# Prototype.net
KiCad netlist of a schematic drawn in EAGLE
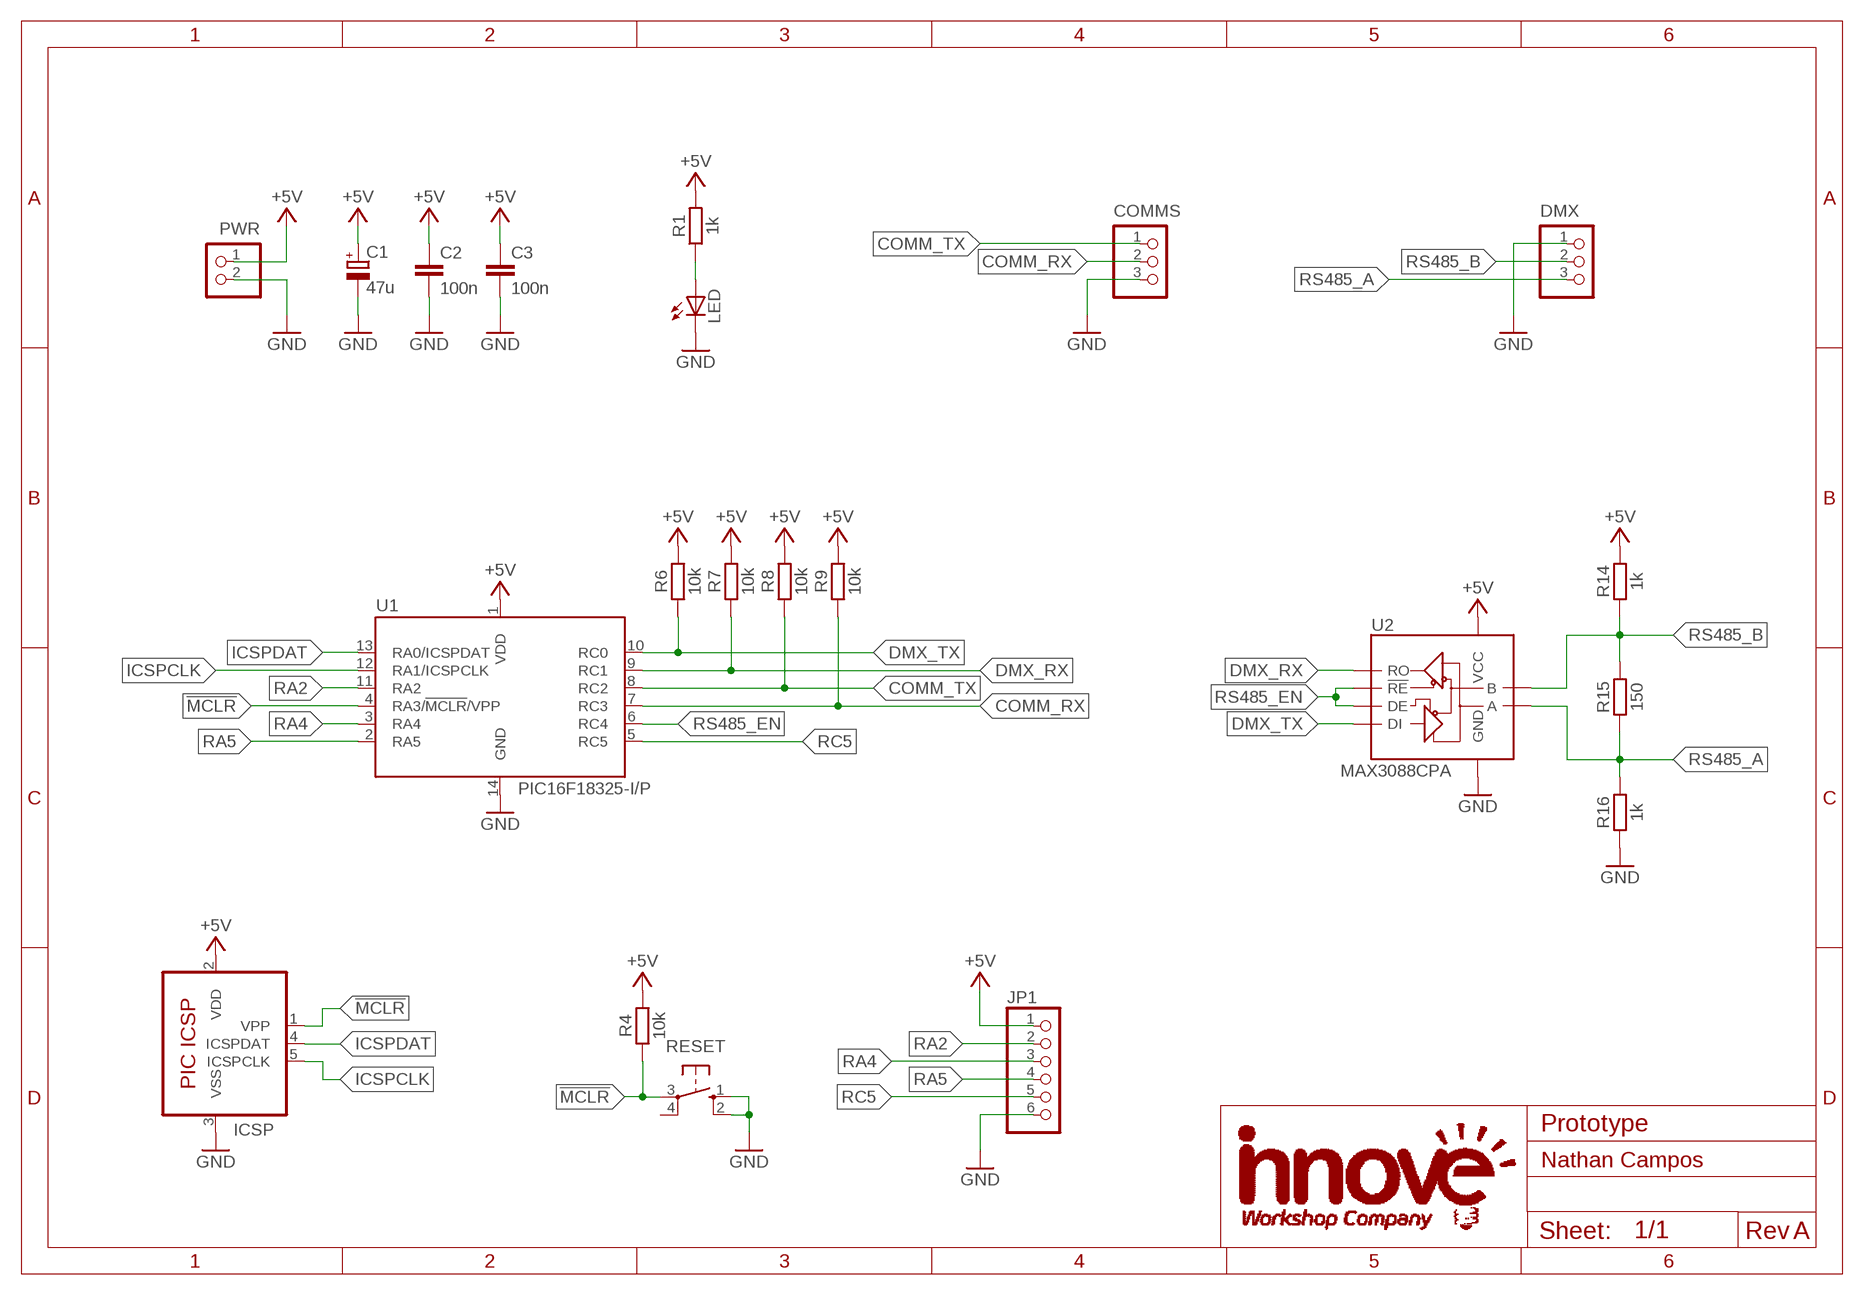
[diagram p0: schematic, sheet 1]

(export (version "E")
  (design (tool "Eeschema 10.0.6"))
  (components
    (comp (ref "C1")
      (value "47u")
      (footprint "eagle-import:E2,5-6")
      (libsource (lib "eagle-import") (part "CPOL-E2.5-6"))
    )
    (comp (ref "C2")
      (value "100n")
      (footprint "eagle-import:C050-025X075")
      (libsource (lib "eagle-import") (part "C5.0-2.5X7.5"))
    )
    (comp (ref "C3")
      (value "100n")
      (footprint "eagle-import:C050-025X075")
      (libsource (lib "eagle-import") (part "C5.0-2.5X7.5"))
    )
    (comp (ref "COMMS")
      (value "B3B-XH-A")
      (footprint "eagle-import:B3B-XH-A")
      (libsource (lib "eagle-import") (part "B3B-XH-A"))
    )
    (comp (ref "DMX")
      (value "B3B-XH-A")
      (footprint "eagle-import:B3B-XH-A")
      (libsource (lib "eagle-import") (part "B3B-XH-A"))
    )
    (comp (ref "ICSP")
      (value "PIC-ICSP-XH6")
      (footprint "eagle-import:B6B-XH-A")
      (libsource (lib "eagle-import") (part "PIC-ICSP-XH6"))
    )
    (comp (ref "JP1")
      (value "PINHD-1X6")
      (footprint "eagle-import:1X06")
      (libsource (lib "eagle-import") (part "PINHD-1X6"))
    )
    (comp (ref "LED")
      (value "LED-JST-XH")
      (footprint "eagle-import:B2B-XH-A")
      (libsource (lib "eagle-import") (part "LED-JST-XH"))
    )
    (comp (ref "PWR")
      (value "B2B-XH-A")
      (footprint "eagle-import:B2B-XH-A")
      (libsource (lib "eagle-import") (part "B2B-XH-A"))
    )
    (comp (ref "R1")
      (value "1k")
      (footprint "eagle-import:0207_10")
      (libsource (lib "eagle-import") (part "RT0207"))
    )
    (comp (ref "R4")
      (value "10k")
      (footprint "eagle-import:0207_10")
      (libsource (lib "eagle-import") (part "RT0207"))
    )
    (comp (ref "R6")
      (value "10k")
      (footprint "eagle-import:0207_10")
      (libsource (lib "eagle-import") (part "RT0207"))
    )
    (comp (ref "R7")
      (value "10k")
      (footprint "eagle-import:0207_10")
      (libsource (lib "eagle-import") (part "RT0207"))
    )
    (comp (ref "R8")
      (value "10k")
      (footprint "eagle-import:0207_10")
      (libsource (lib "eagle-import") (part "RT0207"))
    )
    (comp (ref "R9")
      (value "10k")
      (footprint "eagle-import:0207_10")
      (libsource (lib "eagle-import") (part "RT0207"))
    )
    (comp (ref "R14")
      (value "1k")
      (footprint "eagle-import:0207_10")
      (libsource (lib "eagle-import") (part "RT0207"))
    )
    (comp (ref "R15")
      (value "150")
      (footprint "eagle-import:0207_10")
      (libsource (lib "eagle-import") (part "RT0207"))
    )
    (comp (ref "R16")
      (value "1k")
      (footprint "eagle-import:0207_10")
      (libsource (lib "eagle-import") (part "RT0207"))
    )
    (comp (ref "RESET")
      (value "TACT-4PIN-THT")
      (footprint "eagle-import:B3F-10XX")
      (fields (field (name "MPN") "B3F-1000"))
      (libsource (lib "eagle-import") (part "TACT-4PIN-THT"))
    )
    (comp (ref "U1")
      (value "PIC16F18325-I/P")
      (footprint "eagle-import:DIL14")
      (libsource (lib "eagle-import") (part "PIC16F18325-I/P"))
    )
    (comp (ref "U2")
      (value "MAX3088CPA")
      (footprint "eagle-import:DIP-8")
      (libsource (lib "eagle-import") (part "MAX3088CPA"))
    )
  )
  (nets
    (net (code "1") (name "+5V") (class "Default")
      (node (ref "C1") (pin "+") (pinfunction "+_+") (pintype "passive"))
      (node (ref "C2") (pin "1") (pinfunction "1_1") (pintype "passive"))
      (node (ref "C3") (pin "1") (pinfunction "1_1") (pintype "passive"))
      (node (ref "ICSP") (pin "2") (pinfunction "VDD_2") (pintype "power_in"))
      (node (ref "JP1") (pin "1") (pinfunction "1_1") (pintype "passive"))
      (node (ref "PWR") (pin "1") (pinfunction "1_1") (pintype "passive"))
      (node (ref "R1") (pin "2") (pinfunction "2_2") (pintype "passive"))
      (node (ref "R14") (pin "2") (pinfunction "2_2") (pintype "passive"))
      (node (ref "R4") (pin "2") (pinfunction "2_2") (pintype "passive"))
      (node (ref "R6") (pin "2") (pinfunction "2_2") (pintype "passive"))
      (node (ref "R7") (pin "2") (pinfunction "2_2") (pintype "passive"))
      (node (ref "R8") (pin "2") (pinfunction "2_2") (pintype "passive"))
      (node (ref "R9") (pin "2") (pinfunction "2_2") (pintype "passive"))
      (node (ref "U1") (pin "1") (pinfunction "VDD_1") (pintype "power_in"))
      (node (ref "U2") (pin "8") (pinfunction "VCC_8") (pintype "bidirectional"))
    )
    (net (code "2") (name "/~{MCLR}") (class "Default")
      (node (ref "ICSP") (pin "1") (pinfunction "VPP_1") (pintype "passive"))
      (node (ref "R4") (pin "1") (pinfunction "1_1") (pintype "passive"))
      (node (ref "RESET") (pin "3") (pinfunction "P_3") (pintype "passive"))
      (node (ref "U1") (pin "4") (pinfunction "RA3/~{MCLR}/VPP_4") (pintype "input"))
    )
    (net (code "3") (name "COMM_RX") (class "Default")
      (node (ref "COMMS") (pin "2") (pinfunction "2_2") (pintype "passive"))
      (node (ref "R9") (pin "1") (pinfunction "1_1") (pintype "passive"))
      (node (ref "U1") (pin "7") (pinfunction "RC3_7") (pintype "bidirectional"))
    )
    (net (code "4") (name "COMM_TX") (class "Default")
      (node (ref "COMMS") (pin "1") (pinfunction "1_1") (pintype "passive"))
      (node (ref "R8") (pin "1") (pinfunction "1_1") (pintype "passive"))
      (node (ref "U1") (pin "8") (pinfunction "RC2_8") (pintype "bidirectional"))
    )
    (net (code "5") (name "DMX_RX") (class "Default")
      (node (ref "R7") (pin "1") (pinfunction "1_1") (pintype "passive"))
      (node (ref "U1") (pin "9") (pinfunction "RC1_9") (pintype "bidirectional"))
      (node (ref "U2") (pin "1") (pinfunction "RO_1") (pintype "bidirectional"))
    )
    (net (code "6") (name "DMX_TX") (class "Default")
      (node (ref "R6") (pin "1") (pinfunction "1_1") (pintype "passive"))
      (node (ref "U1") (pin "10") (pinfunction "RC0_10") (pintype "bidirectional"))
      (node (ref "U2") (pin "4") (pinfunction "DI_4") (pintype "bidirectional"))
    )
    (net (code "7") (name "GND") (class "Default")
      (node (ref "C1") (pin "-") (pinfunction "-_-") (pintype "passive"))
      (node (ref "C2") (pin "2") (pinfunction "2_2") (pintype "passive"))
      (node (ref "C3") (pin "2") (pinfunction "2_2") (pintype "passive"))
      (node (ref "COMMS") (pin "3") (pinfunction "3_3") (pintype "passive"))
      (node (ref "DMX") (pin "1") (pinfunction "1_1") (pintype "passive"))
      (node (ref "ICSP") (pin "3") (pinfunction "VSS_3") (pintype "power_in"))
      (node (ref "JP1") (pin "6") (pinfunction "6_6") (pintype "passive"))
      (node (ref "LED") (pin "2") (pinfunction "C_2") (pintype "passive"))
      (node (ref "PWR") (pin "2") (pinfunction "2_2") (pintype "passive"))
      (node (ref "R16") (pin "1") (pinfunction "1_1") (pintype "passive"))
      (node (ref "RESET") (pin "1") (pinfunction "S_1") (pintype "passive"))
      (node (ref "RESET") (pin "2") (pinfunction "S1_2") (pintype "passive"))
      (node (ref "U1") (pin "14") (pinfunction "GND_14") (pintype "power_in"))
      (node (ref "U2") (pin "5") (pinfunction "GND_5") (pintype "bidirectional"))
    )
    (net (code "8") (name "ICSPCLK") (class "Default")
      (node (ref "ICSP") (pin "5") (pinfunction "ICSPCLK_5") (pintype "passive"))
      (node (ref "U1") (pin "12") (pinfunction "RA1/ICSPCLK_12") (pintype "bidirectional"))
    )
    (net (code "9") (name "ICSPDAT") (class "Default")
      (node (ref "ICSP") (pin "4") (pinfunction "ICSPDAT_4") (pintype "passive"))
      (node (ref "U1") (pin "13") (pinfunction "RA0/ICSPDAT_13") (pintype "bidirectional"))
    )
    (net (code "10") (name "Net-(LED-A)") (class "Default")
      (node (ref "LED") (pin "1") (pinfunction "A_1") (pintype "passive"))
      (node (ref "R1") (pin "1") (pinfunction "1_1") (pintype "passive"))
    )
    (net (code "11") (name "RA2") (class "Default")
      (node (ref "JP1") (pin "2") (pinfunction "2_2") (pintype "passive"))
      (node (ref "U1") (pin "11") (pinfunction "RA2_11") (pintype "bidirectional"))
    )
    (net (code "12") (name "RA4") (class "Default")
      (node (ref "JP1") (pin "3") (pinfunction "3_3") (pintype "passive"))
      (node (ref "U1") (pin "3") (pinfunction "RA4_3") (pintype "bidirectional"))
    )
    (net (code "13") (name "RA5") (class "Default")
      (node (ref "JP1") (pin "4") (pinfunction "4_4") (pintype "passive"))
      (node (ref "U1") (pin "2") (pinfunction "RA5_2") (pintype "bidirectional"))
    )
    (net (code "14") (name "RC5") (class "Default")
      (node (ref "JP1") (pin "5") (pinfunction "5_5") (pintype "passive"))
      (node (ref "U1") (pin "5") (pinfunction "RC5_5") (pintype "bidirectional"))
    )
    (net (code "15") (name "RS485_A") (class "Default")
      (node (ref "DMX") (pin "3") (pinfunction "3_3") (pintype "passive"))
      (node (ref "R15") (pin "1") (pinfunction "1_1") (pintype "passive"))
      (node (ref "R16") (pin "2") (pinfunction "2_2") (pintype "passive"))
      (node (ref "U2") (pin "6") (pinfunction "A_6") (pintype "bidirectional"))
    )
    (net (code "16") (name "RS485_B") (class "Default")
      (node (ref "DMX") (pin "2") (pinfunction "2_2") (pintype "passive"))
      (node (ref "R14") (pin "1") (pinfunction "1_1") (pintype "passive"))
      (node (ref "R15") (pin "2") (pinfunction "2_2") (pintype "passive"))
      (node (ref "U2") (pin "7") (pinfunction "B_7") (pintype "bidirectional"))
    )
    (net (code "17") (name "RS485_EN") (class "Default")
      (node (ref "U1") (pin "6") (pinfunction "RC4_6") (pintype "bidirectional"))
      (node (ref "U2") (pin "2") (pinfunction "~{RE}_2") (pintype "bidirectional"))
      (node (ref "U2") (pin "3") (pinfunction "DE_3") (pintype "bidirectional"))
    )
    (net (code "18") (name "unconnected-(RESET-P1-Pad4)") (class "Default")
      (node (ref "RESET") (pin "4") (pinfunction "P1_4") (pintype "passive"))
    )
  )
)
